# front-panel.net
KiCad netlist of a schematic drawn in Altium Designer
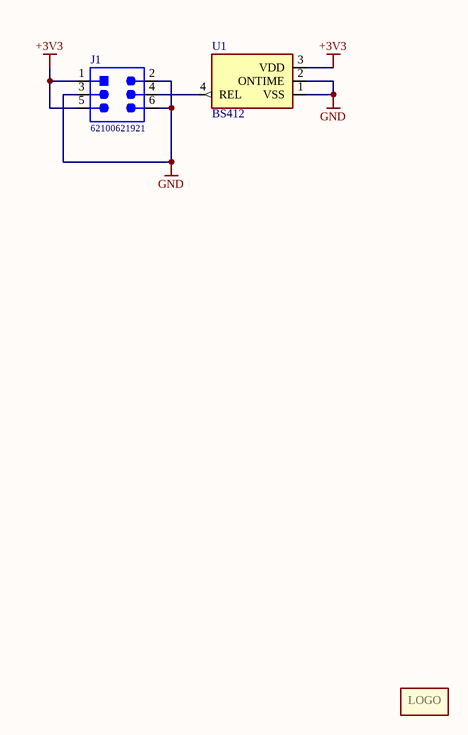
[diagram p0: front-panel.SchDoc]

(export (version "E")
  (design (tool "Eeschema 10.0.6"))
  (components
    (comp (ref "J1")
      (value "62100621921")
      (footprint "62100621921")
      (description "WR-PHD Pin Header, SMT, pitch 2mm, Dual Row, Vertical, 6p")
      (fields (field (name "MANUFACTURER") "Wurth Elektronik") (field (name "JLCPCB PART #") "C3294482"))
      (libsource (lib "7c7 Engineering") (part "Symbol"))
    )
    (comp (ref "M1")
      (value "Logo")
      (footprint "LOGO_9x6mm")
      (libsource (lib "Integrated_Library_LieBtrau") (part "Logo"))
    )
    (comp (ref "U1")
      (value "BS412")
      (footprint "BS412-Footprint-1")
      (description "Mini Basic PIR Sensor - BS412")
      (fields (field (name "JLCPCB PART #") "C410378"))
      (libsource (lib "7c7 Engineering") (part "BS412-Symbol-1"))
    )
  )
  (nets
    (net (code "1") (name "+3V3") (class "Default")
      (node (ref "J1") (pin "1") (pinfunction "1_1") (pintype "passive"))
      (node (ref "J1") (pin "5") (pinfunction "5_5") (pintype "passive"))
      (node (ref "U1") (pin "3") (pinfunction "VDD_3") (pintype "power_in"))
    )
    (net (code "2") (name "GND") (class "Default")
      (node (ref "J1") (pin "2") (pinfunction "2_2") (pintype "passive"))
      (node (ref "J1") (pin "3") (pinfunction "3_3") (pintype "passive"))
      (node (ref "J1") (pin "6") (pinfunction "6_6") (pintype "passive"))
      (node (ref "U1") (pin "1") (pinfunction "VSS_1") (pintype "power_in"))
      (node (ref "U1") (pin "2") (pinfunction "ONTIME_2") (pintype "passive"))
    )
    (net (code "3") (name "Net-(U1-REL)") (class "Default")
      (node (ref "J1") (pin "4") (pinfunction "4_4") (pintype "passive"))
      (node (ref "U1") (pin "4") (pinfunction "REL_4") (pintype "output"))
    )
  )
)
